# Power.net
KiCad netlist of a schematic drawn in Altium Designer
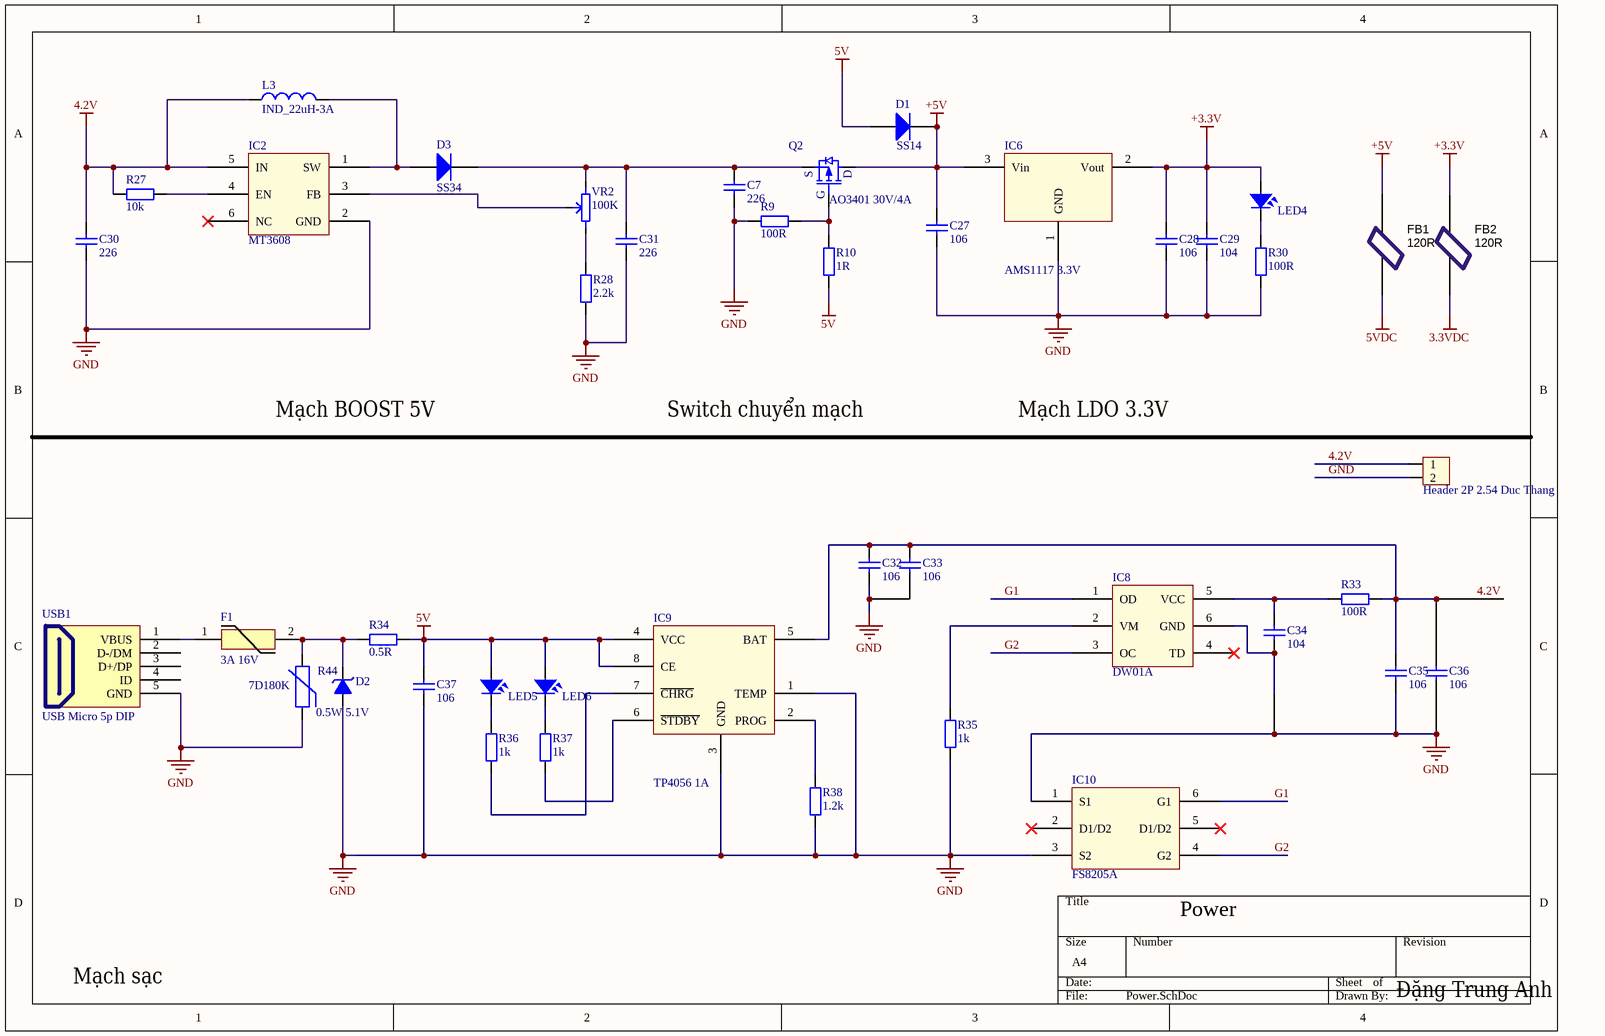
[diagram p0: Power.SchDoc]

(export (version "E")
  (design (tool "Eeschema 10.0.6"))
  (components
    (comp (ref "C7")
      (value "226")
      (footprint "tu 0805")
      (description "Dán")
      (libsource (lib "Altium_Lib_by_KhueNguyenCreator") (part "Tu 0805 226 16V 20%"))
    )
    (comp (ref "C27")
      (value "106")
      (footprint "Tu 0805")
      (description "Dán")
      (libsource (lib "THU VIEN SCH") (part "Tu 0805 106 16V 10%"))
    )
    (comp (ref "C28")
      (value "106")
      (footprint "Tu 0805")
      (description "Dán")
      (libsource (lib "THU VIEN SCH") (part "Tu 0805 106 16V 10%"))
    )
    (comp (ref "C29")
      (value "104")
      (footprint "tu 0805")
      (description "Dán")
      (libsource (lib "THU VIEN SCH") (part "Tu 0805 104 50V 10%"))
    )
    (comp (ref "C30")
      (value "226")
      (footprint "tu 0805")
      (description "Dán")
      (libsource (lib "*") (part "Tu 0805 226 16V 20%"))
    )
    (comp (ref "C31")
      (value "226")
      (footprint "tu 0805")
      (description "Dán")
      (libsource (lib "Altium_Lib_by_KhueNguyenCreator") (part "Tu 0805 226 16V 20%"))
    )
    (comp (ref "C32")
      (value "106")
      (footprint "tu 0805")
      (description "Dán")
      (libsource (lib "Altium_Lib_by_KhueNguyenCreator") (part "Tu 0805 106 16V 10%"))
    )
    (comp (ref "C33")
      (value "106")
      (footprint "Tu 0805")
      (description "Dán")
      (libsource (lib "THU VIEN SCH") (part "Tu 0805 106 16V 10%"))
    )
    (comp (ref "C34")
      (value "104")
      (footprint "tu 0805")
      (description "Dán")
      (libsource (lib "THU VIEN SCH") (part "Tu 0805 104 50V 10%"))
    )
    (comp (ref "C35")
      (value "106")
      (footprint "Tu 0805")
      (description "Dán")
      (libsource (lib "THU VIEN SCH") (part "Tu 0805 106 16V 10%"))
    )
    (comp (ref "C36")
      (value "106")
      (footprint "Tu 0805")
      (description "Dán")
      (libsource (lib "THU VIEN SCH") (part "Tu 0805 106 16V 10%"))
    )
    (comp (ref "C37")
      (value "106")
      (footprint "Tu 0805")
      (description "Dán")
      (libsource (lib "THU VIEN SCH") (part "Tu 0805 106 16V 10%"))
    )
    (comp (ref "D1")
      (value "SS14")
      (footprint "DIODE SMA")
      (description "Dán")
      (libsource (lib "Altium_Lib_by_KhueNguyenCreator") (part "Diode SS14 ( 1N5819)"))
    )
    (comp (ref "D2")
      (value "0.5W 5.1V")
      (footprint "DIODE ZENNER SMD SOD80")
      (description "Dán")
      (libsource (lib "Altium_Lib_by_KhueNguyenCreator") (part "Diode Zener 5.1V"))
    )
    (comp (ref "D3")
      (value "SS34")
      (footprint "DIODE SMA")
      (description "Dán")
      (libsource (lib "Altium_Lib_by_KhueNguyenCreator") (part "Diode SS34 ( 1N5822 )"))
    )
    (comp (ref "F1")
      (value "3A 16V")
      (footprint "FUSE-RUEF250U-2")
      (description "FUSE POLYSWITCH RUE SERIES 3A 16V")
      (fields (field (name "MPN") "RUEF250U-2"))
      (libsource (lib "BYTECH_HW_LIB_2019 (1)") (part "Cau chi tu phuc hoi 3A 16V"))
    )
    (comp (ref "FB1")
      (value "120R")
      (footprint "INDC1608N")
      (description "Ferrite bead 120 Ohm at 100 MHz 2A 0603 SMD")
      (libsource (lib "My library altium") (part "FERRITE_120R_2.5A-0603"))
    )
    (comp (ref "FB2")
      (value "120R")
      (footprint "INDC1608N")
      (description "Ferrite bead 120 Ohm at 100 MHz 2A 0603 SMD")
      (libsource (lib "My library altium") (part "FERRITE_120R_2.5A-0603"))
    )
    (comp (ref "H2")
      (value "Header 2P 2.54 Duc Thang")
      (footprint "XH2.54M-2")
      (description "Cắm")
      (libsource (lib "Altium_Lib_by_KhueNguyenCreator") (part "Header 2P 2.54 Duc Thang"))
    )
    (comp (ref "IC2")
      (value "MT3608")
      (footprint "SOT23-6A")
      (libsource (lib "Integrated_Library") (part "MT3608_Boost"))
    )
    (comp (ref "IC6")
      (value "AMS1117 3.3V")
      (footprint "SOT223")
      (libsource (lib "Integrated_Library") (part "AMS1117 3.3V"))
    )
    (comp (ref "IC8")
      (value "DW01A")
      (footprint "SOT23127P600-8N")
      (libsource (lib "Integrated_Library") (part "DW01A"))
    )
    (comp (ref "IC9")
      (value "TP4056 1A")
      (footprint "SOP8")
      (libsource (lib "Integrated_Library") (part "TP4056 1A"))
    )
    (comp (ref "IC10")
      (value "FS8205A")
      (footprint "SOT-23-6L")
      (libsource (lib "Integrated_Library") (part "FS8205A"))
    )
    (comp (ref "L3")
      (value "IND_22uH-3A")
      (footprint "IND_22_12X12_SMD")
      (description "Fixed Inductors MSS1038 SMT Shielded 15 uH 20 % 3.8 A")
      (fields
        (field (name "MANUFACTURER") "Bourns")
        (field (name "MANUFACTURER PART NUMBER") "MSS1038-153MLC")
      )
      (libsource (lib "Altium_Lib_by_KhueNguyenCreator") (part "IND_22uH-3A-30%-SMD_1"))
    )
    (comp (ref "LED4")
      (value "LED SMD")
      (footprint "SM-LED-0805-Red")
      (libsource (lib "syhaunguyen") (part "LED-SMD-0805"))
    )
    (comp (ref "LED5")
      (value "LED SMD")
      (footprint "SM-LED-0805-Red")
      (libsource (lib "syhaunguyen") (part "LED-SMD-0805"))
    )
    (comp (ref "LED6")
      (value "LED SMD")
      (footprint "SM-LED-0805-Blue")
      (libsource (lib "syhaunguyen") (part "LED-SMD-0805"))
    )
    (comp (ref "Q2")
      (value "AO3401 30V/4A")
      (footprint "SOT23_3")
      (description "MOSFET P-CH 30V 4A SOT23")
      (fields (field (name "MPN") "AO3415") (field (name "MFR") "Alpha & Omega Semiconductor Inc."))
      (libsource (lib "BYTECH_HW_LIB_2019 (1)") (part "AO3401"))
    )
    (comp (ref "R9")
      (value "100R")
      (footprint "tro smd 0805")
      (description "Dán")
      (libsource (lib "Altium_Lib_by_KhueNguyenCreator") (part "Tro 0805 5% 100R"))
    )
    (comp (ref "R10")
      (value "1R")
      (footprint "tro smd 0805")
      (description "Dán")
      (libsource (lib "THU VIEN SCH") (part "Tro 0805 1% 1R"))
    )
    (comp (ref "R27")
      (value "10k")
      (footprint "tro smd 0805")
      (description "Dán")
      (libsource (lib "THU VIEN SCH") (part "Tro 0805 5% 10k"))
    )
    (comp (ref "R28")
      (value "2.2k")
      (footprint "tro smd 0805")
      (description "Dán")
      (libsource (lib "Altium_Lib_by_KhueNguyenCreator") (part "Tro 0805 5% 2.2k"))
    )
    (comp (ref "R30")
      (value "100R")
      (footprint "tro smd 0805")
      (description "Dán")
      (libsource (lib "Ban2") (part "Tro 0805 5% 100R"))
    )
    (comp (ref "R33")
      (value "100R")
      (footprint "tro smd 0805")
      (description "Dán")
      (libsource (lib "THU VIEN SCH") (part "Tro 0805 5% 100R"))
    )
    (comp (ref "R34")
      (value "0.5R")
      (footprint "tro smd 0805")
      (description "Dán")
      (libsource (lib "THU VIEN SCH") (part "Tro 0805 5% 0.5R"))
    )
    (comp (ref "R35")
      (value "1k")
      (footprint "tro smd 0805")
      (description "Dán")
      (libsource (lib "THU VIEN SCH") (part "Tro 0805 5% 1k"))
    )
    (comp (ref "R36")
      (value "1k")
      (footprint "tro smd 0805")
      (description "Dán")
      (libsource (lib "THU VIEN SCH") (part "Tro 0805 5% 1k"))
    )
    (comp (ref "R37")
      (value "1k")
      (footprint "tro smd 0805")
      (description "Dán")
      (libsource (lib "THU VIEN SCH") (part "Tro 0805 5% 1k"))
    )
    (comp (ref "R38")
      (value "1.2k")
      (footprint "tro smd 0805")
      (description "Dán")
      (libsource (lib "THU VIEN SCH") (part "Tro 0805 5% 1.2k"))
    )
    (comp (ref "R44")
      (value "7D180K")
      (footprint "VARISTOR-7D180K")
      (description "VARISTOR 7V 18A DISC 7MM")
      (fields (field (name "MPN") "V47ZA1P"))
      (libsource (lib "BYTECH_HW_LIB_2019 (1)") (part "Varistor 7D180K"))
    )
    (comp (ref "USB1")
      (value "USB Micro 5p DIP")
      (footprint "USB Micro 5p DIP")
      (description "USB Type B")
      (libsource (lib "Altium_Lib_by_KhueNguyenCreator") (part "USB Micro 5p DIP"))
    )
    (comp (ref "VR2")
      (value "100K")
      (footprint "Bien Tro Tam Giac Dung")
      (description "Cắm")
      (libsource (lib "Altium_Lib_by_KhueNguyenCreator") (part "Bien tro tam giac 100K Dung"))
    )
  )
  (nets
    (net (code "1") (name "+3.3V") (class "Default")
      (node (ref "C28") (pin "1") (pinfunction "1_1") (pintype "passive"))
      (node (ref "C29") (pin "1") (pinfunction "1_1") (pintype "passive"))
      (node (ref "FB2") (pin "1") (pinfunction "1_1") (pintype "passive"))
      (node (ref "IC6") (pin "2") (pinfunction "Vout_2") (pintype "passive"))
      (node (ref "LED4") (pin "1") (pinfunction "1_1") (pintype "passive"))
    )
    (net (code "2") (name "+5V") (class "Default")
      (node (ref "C27") (pin "1") (pinfunction "1_1") (pintype "passive"))
      (node (ref "D1") (pin "2") (pinfunction "K_2") (pintype "passive"))
      (node (ref "FB1") (pin "1") (pinfunction "1_1") (pintype "passive"))
      (node (ref "IC6") (pin "3") (pinfunction "Vin_3") (pintype "passive"))
      (node (ref "Q2") (pin "3") (pinfunction "D_3") (pintype "passive"))
    )
    (net (code "3") (name "/G1") (class "Default")
      (node (ref "IC10") (pin "6") (pinfunction "G1_6") (pintype "passive"))
      (node (ref "IC8") (pin "1") (pinfunction "OD_1") (pintype "passive"))
    )
    (net (code "4") (name "/G2") (class "Default")
      (node (ref "IC10") (pin "4") (pinfunction "G2_4") (pintype "passive"))
      (node (ref "IC8") (pin "3") (pinfunction "OC_3") (pintype "passive"))
    )
    (net (code "5") (name "3.3VDC") (class "Default")
      (node (ref "FB2") (pin "2") (pinfunction "2_2") (pintype "passive"))
    )
    (net (code "6") (name "4.2V") (class "Default")
      (node (ref "C30") (pin "1") (pinfunction "1_1") (pintype "passive"))
      (node (ref "C32") (pin "2") (pinfunction "2_2") (pintype "passive"))
      (node (ref "C33") (pin "1") (pinfunction "1_1") (pintype "passive"))
      (node (ref "C35") (pin "1") (pinfunction "1_1") (pintype "passive"))
      (node (ref "C36") (pin "1") (pinfunction "1_1") (pintype "passive"))
      (node (ref "H2") (pin "1") (pinfunction "1_1") (pintype "passive"))
      (node (ref "IC2") (pin "5") (pinfunction "IN_5") (pintype "passive"))
      (node (ref "IC9") (pin "5") (pinfunction "BAT_5") (pintype "passive"))
      (node (ref "L3") (pin "1") (pinfunction "1_1") (pintype "passive"))
      (node (ref "R27") (pin "2") (pinfunction "2_2") (pintype "passive"))
      (node (ref "R33") (pin "2") (pinfunction "2_2") (pintype "passive"))
    )
    (net (code "7") (name "5V") (class "Default")
      (node (ref "C37") (pin "1") (pinfunction "1_1") (pintype "passive"))
      (node (ref "D1") (pin "1") (pinfunction "A_1") (pintype "passive"))
      (node (ref "IC9") (pin "4") (pinfunction "VCC_4") (pintype "passive"))
      (node (ref "IC9") (pin "8") (pinfunction "CE_8") (pintype "passive"))
      (node (ref "LED5") (pin "1") (pinfunction "1_1") (pintype "passive"))
      (node (ref "LED6") (pin "1") (pinfunction "1_1") (pintype "passive"))
      (node (ref "R10") (pin "1") (pinfunction "1_1") (pintype "passive"))
      (node (ref "R34") (pin "2") (pinfunction "2_2") (pintype "passive"))
    )
    (net (code "8") (name "5VDC") (class "Default")
      (node (ref "FB1") (pin "2") (pinfunction "2_2") (pintype "passive"))
    )
    (net (code "9") (name "GND") (class "Default")
      (node (ref "C27") (pin "2") (pinfunction "2_2") (pintype "passive"))
      (node (ref "C28") (pin "2") (pinfunction "2_2") (pintype "passive"))
      (node (ref "C29") (pin "2") (pinfunction "2_2") (pintype "passive"))
      (node (ref "C30") (pin "2") (pinfunction "2_2") (pintype "passive"))
      (node (ref "C31") (pin "2") (pinfunction "2_2") (pintype "passive"))
      (node (ref "C32") (pin "1") (pinfunction "1_1") (pintype "passive"))
      (node (ref "C33") (pin "2") (pinfunction "2_2") (pintype "passive"))
      (node (ref "C34") (pin "1") (pinfunction "1_1") (pintype "passive"))
      (node (ref "C35") (pin "2") (pinfunction "2_2") (pintype "passive"))
      (node (ref "C36") (pin "2") (pinfunction "2_2") (pintype "passive"))
      (node (ref "C37") (pin "2") (pinfunction "2_2") (pintype "passive"))
      (node (ref "C7") (pin "2") (pinfunction "2_2") (pintype "passive"))
      (node (ref "D2") (pin "1") (pinfunction "A_1") (pintype "passive"))
      (node (ref "H2") (pin "2") (pinfunction "2_2") (pintype "passive"))
      (node (ref "IC10") (pin "1") (pinfunction "S1_1") (pintype "passive"))
      (node (ref "IC10") (pin "3") (pinfunction "S2_3") (pintype "passive"))
      (node (ref "IC2") (pin "2") (pinfunction "GND_2") (pintype "passive"))
      (node (ref "IC6") (pin "1") (pinfunction "GND_1") (pintype "passive"))
      (node (ref "IC8") (pin "6") (pinfunction "GND_6") (pintype "passive"))
      (node (ref "IC9") (pin "1") (pinfunction "TEMP_1") (pintype "passive"))
      (node (ref "IC9") (pin "3") (pinfunction "GND_3") (pintype "passive"))
      (node (ref "R28") (pin "1") (pinfunction "1_1") (pintype "passive"))
      (node (ref "R30") (pin "1") (pinfunction "1_1") (pintype "passive"))
      (node (ref "R35") (pin "1") (pinfunction "1_1") (pintype "passive"))
      (node (ref "R38") (pin "1") (pinfunction "1_1") (pintype "passive"))
      (node (ref "R44") (pin "1") (pinfunction "1_1") (pintype "passive"))
      (node (ref "R9") (pin "1") (pinfunction "1_1") (pintype "passive"))
      (node (ref "USB1") (pin "5") (pinfunction "GND_5") (pintype "passive"))
    )
    (net (code "10") (name "Net-(D2-K)") (class "Default")
      (node (ref "D2") (pin "2") (pinfunction "K_2") (pintype "passive"))
      (node (ref "F1") (pin "2") (pinfunction "2_2") (pintype "passive"))
      (node (ref "R34") (pin "1") (pinfunction "1_1") (pintype "passive"))
      (node (ref "R44") (pin "2") (pinfunction "2_2") (pintype "passive"))
    )
    (net (code "11") (name "Net-(D3-A)") (class "Default")
      (node (ref "D3") (pin "1") (pinfunction "A_1") (pintype "passive"))
      (node (ref "IC2") (pin "1") (pinfunction "SW_1") (pintype "passive"))
      (node (ref "L3") (pin "2") (pinfunction "2_2") (pintype "passive"))
    )
    (net (code "12") (name "Net-(D3-K)") (class "Default")
      (node (ref "C31") (pin "1") (pinfunction "1_1") (pintype "passive"))
      (node (ref "C7") (pin "1") (pinfunction "1_1") (pintype "passive"))
      (node (ref "D3") (pin "2") (pinfunction "K_2") (pintype "passive"))
      (node (ref "Q2") (pin "2") (pinfunction "S_2") (pintype "passive"))
      (node (ref "VR2") (pin "3") (pinfunction "3_3") (pintype "passive"))
    )
    (net (code "13") (name "Net-(IC2-EN)") (class "Default")
      (node (ref "IC2") (pin "4") (pinfunction "EN_4") (pintype "passive"))
      (node (ref "R27") (pin "1") (pinfunction "1_1") (pintype "passive"))
    )
    (net (code "14") (name "Net-(IC2-FB)") (class "Default")
      (node (ref "IC2") (pin "3") (pinfunction "FB_3") (pintype "passive"))
      (node (ref "VR2") (pin "2") (pinfunction "2_2") (pintype "passive"))
    )
    (net (code "15") (name "Net-(IC8-VCC)") (class "Default")
      (node (ref "C34") (pin "2") (pinfunction "2_2") (pintype "passive"))
      (node (ref "IC8") (pin "5") (pinfunction "VCC_5") (pintype "passive"))
      (node (ref "R33") (pin "1") (pinfunction "1_1") (pintype "passive"))
    )
    (net (code "16") (name "Net-(IC8-VM)") (class "Default")
      (node (ref "IC8") (pin "2") (pinfunction "VM_2") (pintype "passive"))
      (node (ref "R35") (pin "2") (pinfunction "2_2") (pintype "passive"))
    )
    (net (code "17") (name "Net-(IC9-PROG)") (class "Default")
      (node (ref "IC9") (pin "2") (pinfunction "PROG_2") (pintype "passive"))
      (node (ref "R38") (pin "2") (pinfunction "2_2") (pintype "passive"))
    )
    (net (code "18") (name "Net-(IC9-~{CHRG})") (class "Default")
      (node (ref "IC9") (pin "7") (pinfunction "~{CHRG}_7") (pintype "passive"))
      (node (ref "R36") (pin "1") (pinfunction "1_1") (pintype "passive"))
    )
    (net (code "19") (name "Net-(IC9-~{STDBY})") (class "Default")
      (node (ref "IC9") (pin "6") (pinfunction "~{STDBY}_6") (pintype "passive"))
      (node (ref "R37") (pin "1") (pinfunction "1_1") (pintype "passive"))
    )
    (net (code "20") (name "Net-(LED4-Pad2)") (class "Default")
      (node (ref "LED4") (pin "2") (pinfunction "2_2") (pintype "passive"))
      (node (ref "R30") (pin "2") (pinfunction "2_2") (pintype "passive"))
    )
    (net (code "21") (name "Net-(LED5-Pad2)") (class "Default")
      (node (ref "LED5") (pin "2") (pinfunction "2_2") (pintype "passive"))
      (node (ref "R36") (pin "2") (pinfunction "2_2") (pintype "passive"))
    )
    (net (code "22") (name "Net-(LED6-Pad2)") (class "Default")
      (node (ref "LED6") (pin "2") (pinfunction "2_2") (pintype "passive"))
      (node (ref "R37") (pin "2") (pinfunction "2_2") (pintype "passive"))
    )
    (net (code "23") (name "Net-(Q2-G)") (class "Default")
      (node (ref "Q2") (pin "1") (pinfunction "G_1") (pintype "passive"))
      (node (ref "R10") (pin "2") (pinfunction "2_2") (pintype "passive"))
      (node (ref "R9") (pin "2") (pinfunction "2_2") (pintype "passive"))
    )
    (net (code "24") (name "Net-(R28-Pad2)") (class "Default")
      (node (ref "R28") (pin "2") (pinfunction "2_2") (pintype "passive"))
      (node (ref "VR2") (pin "1") (pinfunction "1_1") (pintype "passive"))
    )
    (net (code "25") (name "Net-(USB1-VBUS)") (class "Default")
      (node (ref "F1") (pin "1") (pinfunction "1_1") (pintype "passive"))
      (node (ref "USB1") (pin "1") (pinfunction "VBUS_1") (pintype "passive"))
    )
    (net (code "26") (name "unconnected-(IC2-NC-Pad6)") (class "Default")
      (node (ref "IC2") (pin "6") (pinfunction "NC_6") (pintype "passive+no_connect"))
    )
    (net (code "27") (name "unconnected-(IC8-TD-Pad4)") (class "Default")
      (node (ref "IC8") (pin "4") (pinfunction "TD_4") (pintype "passive+no_connect"))
    )
    (net (code "28") (name "unconnected-(IC10-D1{slash}D2-Pad2)") (class "Default")
      (node (ref "IC10") (pin "2") (pinfunction "D1/D2_2") (pintype "passive+no_connect"))
    )
    (net (code "29") (name "unconnected-(IC10-D1{slash}D2-Pad5)") (class "Default")
      (node (ref "IC10") (pin "5") (pinfunction "D1/D2_5") (pintype "passive+no_connect"))
    )
    (net (code "30") (name "unconnected-(USB1-D+{slash}DP-Pad3)") (class "Default")
      (node (ref "USB1") (pin "3") (pinfunction "D+/DP_3") (pintype "passive"))
    )
    (net (code "31") (name "unconnected-(USB1-D-{slash}DM-Pad2)") (class "Default")
      (node (ref "USB1") (pin "2") (pinfunction "D-/DM_2") (pintype "passive"))
    )
    (net (code "32") (name "unconnected-(USB1-ID-Pad4)") (class "Default")
      (node (ref "USB1") (pin "4") (pinfunction "ID_4") (pintype "passive"))
    )
  )
)
